# ST_Link.net
KiCad netlist of a schematic drawn in Altium Designer
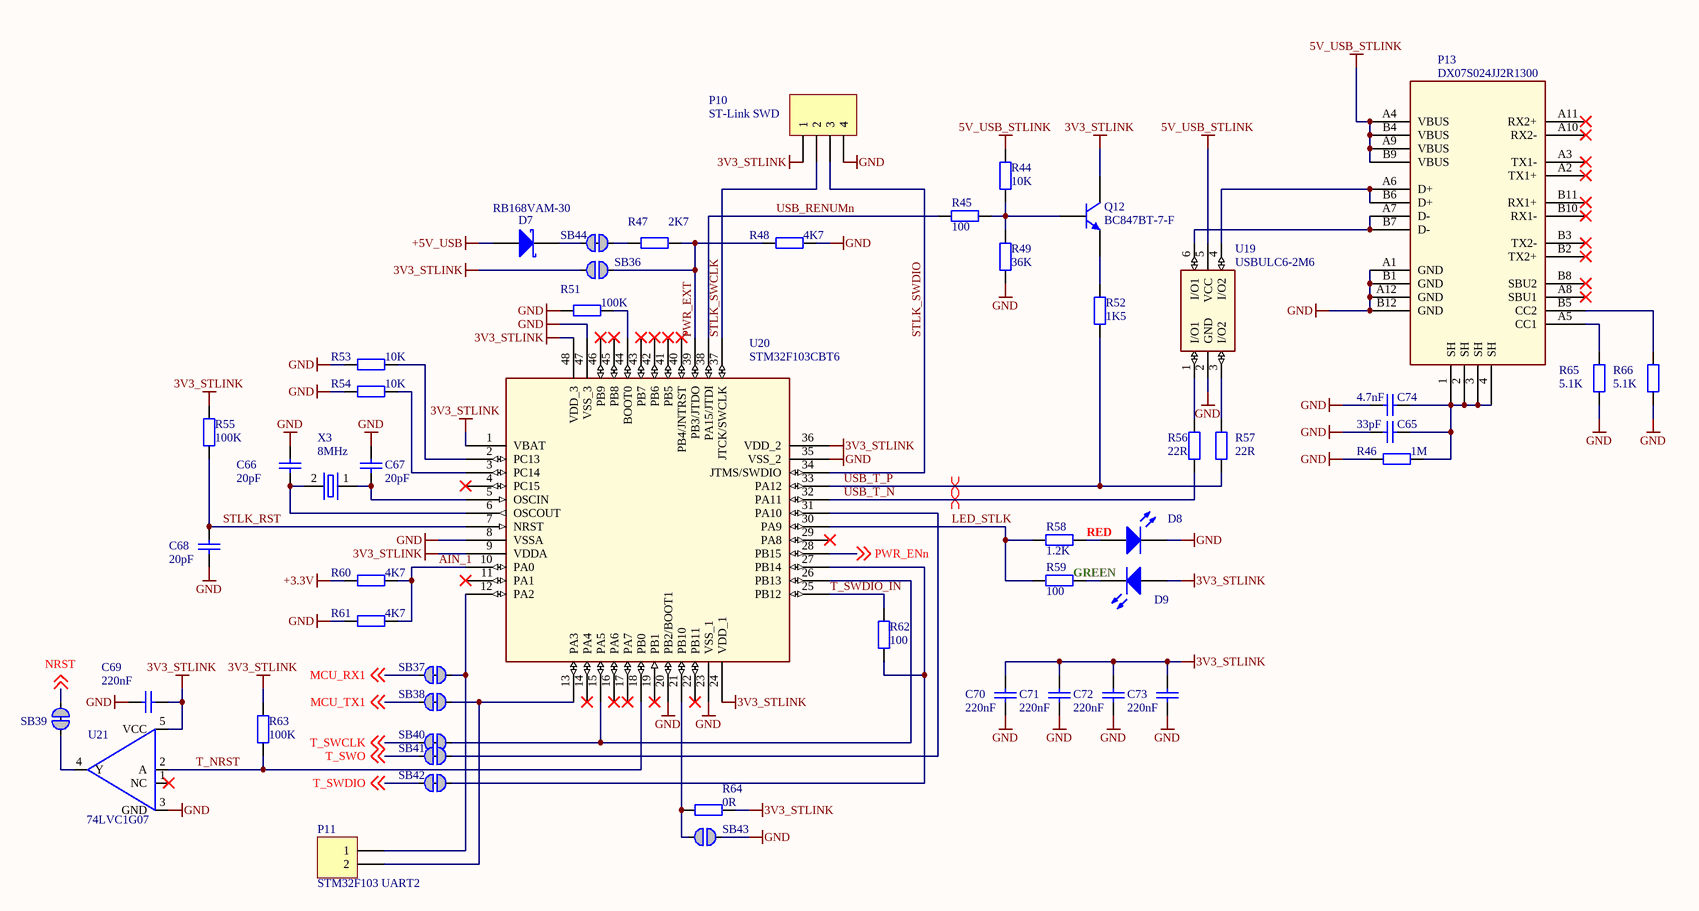
[diagram p0: ST Link.SchDoc]

(export (version "E")
  (design (tool "Eeschema 10.0.6"))
  (components
    (comp (ref "C65")
      (value "33pF")
      (footprint "C0402")
      (description "Capacitor (Semiconductor SIM Model)")
      (fields
        (field (name "MANUFACTURER") "YAGEO")
        (field (name "MANUFACTURER PART NO.") "CC0402JRNPO9BN100")
      )
      (libsource (lib "Miscellaneous Devices") (part "Cap Semi"))
    )
    (comp (ref "C66")
      (value "20pF")
      (footprint "C0402")
      (description "Capacitor (Semiconductor SIM Model)")
      (fields
        (field (name "MANUFACTURER") "YAGEO")
        (field (name "MANUFACTURER PART NO.") "CC0402JRNPO9BN100")
      )
      (libsource (lib "Miscellaneous Devices") (part "Cap Semi"))
    )
    (comp (ref "C67")
      (value "20pF")
      (footprint "C0402")
      (description "Capacitor (Semiconductor SIM Model)")
      (fields
        (field (name "MANUFACTURER") "YAGEO")
        (field (name "MANUFACTURER PART NO.") "CC0402JRNPO9BN100")
      )
      (libsource (lib "Miscellaneous Devices") (part "Cap Semi"))
    )
    (comp (ref "C68")
      (value "20pF")
      (footprint "C0402")
      (description "Capacitor (Semiconductor SIM Model)")
      (fields
        (field (name "MANUFACTURER") "YAGEO")
        (field (name "MANUFACTURER PART NO.") "CC0402JRNPO9BN100")
      )
      (libsource (lib "Miscellaneous Devices") (part "Cap Semi"))
    )
    (comp (ref "C69")
      (value "220nF")
      (footprint "C0402")
      (description "Capacitor (Semiconductor SIM Model)")
      (fields
        (field (name "MANUFACTURER") "YAGEO")
        (field (name "MANUFACTURER PART NO.") "CC0402JRNPO9BN100")
      )
      (libsource (lib "Miscellaneous Devices") (part "Cap Semi"))
    )
    (comp (ref "C70")
      (value "220nF")
      (footprint "C0402")
      (description "Capacitor (Semiconductor SIM Model)")
      (fields
        (field (name "MANUFACTURER") "YAGEO")
        (field (name "MANUFACTURER PART NO.") "CC0402JRNPO9BN100")
      )
      (libsource (lib "Miscellaneous Devices") (part "Cap Semi"))
    )
    (comp (ref "C71")
      (value "220nF")
      (footprint "C0402")
      (description "Capacitor (Semiconductor SIM Model)")
      (fields
        (field (name "MANUFACTURER") "YAGEO")
        (field (name "MANUFACTURER PART NO.") "CC0402JRNPO9BN100")
      )
      (libsource (lib "Miscellaneous Devices") (part "Cap Semi"))
    )
    (comp (ref "C72")
      (value "220nF")
      (footprint "C0402")
      (description "Capacitor (Semiconductor SIM Model)")
      (fields
        (field (name "MANUFACTURER") "YAGEO")
        (field (name "MANUFACTURER PART NO.") "CC0402JRNPO9BN100")
      )
      (libsource (lib "Miscellaneous Devices") (part "Cap Semi"))
    )
    (comp (ref "C73")
      (value "220nF")
      (footprint "C0402")
      (description "Capacitor (Semiconductor SIM Model)")
      (fields
        (field (name "MANUFACTURER") "YAGEO")
        (field (name "MANUFACTURER PART NO.") "CC0402JRNPO9BN100")
      )
      (libsource (lib "Miscellaneous Devices") (part "Cap Semi"))
    )
    (comp (ref "C74")
      (value "4.7nF")
      (footprint "C0402")
      (description "Capacitor (Semiconductor SIM Model)")
      (fields
        (field (name "MANUFACTURER") "YAGEO")
        (field (name "MANUFACTURER PART NO.") "CC0402JRNPO9BN100")
      )
      (libsource (lib "Miscellaneous Devices") (part "Cap Semi"))
    )
    (comp (ref "D7")
      (value "RB168VAM-30")
      (footprint "SOD323")
      (description "Schottky Diode")
      (fields (field (name "MANUFACTURER") "ROHM"))
      (libsource (lib "Miscellaneous Devices") (part "D Schottky"))
    )
    (comp (ref "D8")
      (value "LED")
      (footprint "PICOLED")
      (description "Typical SMD LED")
      (fields (field (name "MANUFACTURER") "ROHM") (field (name "MANUFACTURER PART NO.") "SML-P12UTT86"))
      (libsource (lib "Miscellaneous Devices") (part "LED2"))
    )
    (comp (ref "D9")
      (value "LED")
      (footprint "PICOLED")
      (description "Typical SMD LED")
      (fields (field (name "MANUFACTURER") "ROHM") (field (name "MANUFACTURER PART NO.") "SML-P13PTT86R"))
      (libsource (lib "Miscellaneous Devices") (part "LED2"))
    )
    (comp (ref "P10")
      (value "ST-Link SWD")
      (footprint "HDR1X4")
      (description "Header, 4-Pin")
      (libsource (lib "Miscellaneous Connectors") (part "Header 4"))
    )
    (comp (ref "P11")
      (value "STM32F103 UART2")
      (footprint "HDR1X2")
      (description "Header, 2-Pin")
      (libsource (lib "Miscellaneous Connectors") (part "Header 2"))
    )
    (comp (ref "P13")
      (value "DX07S024JJ2R1300")
      (footprint "DX07_USB_C")
      (description "24P USB C DUAL SMT ON BOARD")
      (fields (field (name "MANUFACTURER") "JAE"))
      (libsource (lib "DX07S024JJ2R1300") (part "DX07S024JJ2R1300"))
    )
    (comp (ref "Q12")
      (value "BC847BT-7-F")
      (footprint "SOT-523_custom")
      (description "NPN Bipolar Transistor")
      (fields
        (field (name "MANUFACTURER") "Diodes Inc.")
        (field (name "MANUFACTURER PART NO.") "BC847AT-7-F")
      )
      (libsource (lib "RUT2CLOUDPrjPcb") (part "NPN"))
    )
    (comp (ref "R44")
      (value "10K")
      (footprint "R0402")
      (fields
        (field (name "MANUFACTURER") "ASJ")
        (field (name "MANUFACTURER PART NO.") "CR10-103-JK")
        (field (name "Comment") "Res2")
      )
      (libsource (lib "Miscellaneous Devices") (part "Res2"))
    )
    (comp (ref "R45")
      (value "100")
      (footprint "R0402")
      (fields
        (field (name "MANUFACTURER") "ASJ")
        (field (name "MANUFACTURER PART NO.") "CR10-103-JK")
        (field (name "Comment") "Res2")
      )
      (libsource (lib "") (part "Res2_2"))
    )
    (comp (ref "R46")
      (value "1M")
      (footprint "R0402")
      (fields
        (field (name "MANUFACTURER") "YAGEO")
        (field (name "MANUFACTURER PART NO.") "RC0402FR-070RL")
        (field (name "Comment") "Res2")
      )
      (libsource (lib "") (part "Res2_1"))
    )
    (comp (ref "R47")
      (value "2K7")
      (footprint "R0402")
      (fields
        (field (name "MANUFACTURER") "ASJ")
        (field (name "MANUFACTURER PART NO.") "CR10-103-JK")
        (field (name "Comment") "Res2")
      )
      (libsource (lib "") (part "Res2_2"))
    )
    (comp (ref "R48")
      (value "4K7")
      (footprint "R0402")
      (fields
        (field (name "MANUFACTURER") "ASJ")
        (field (name "MANUFACTURER PART NO.") "CR10-103-JK")
        (field (name "Comment") "Res2")
      )
      (libsource (lib "") (part "Res2_2"))
    )
    (comp (ref "R49")
      (value "36K")
      (footprint "R0402")
      (fields
        (field (name "MANUFACTURER") "ASJ")
        (field (name "MANUFACTURER PART NO.") "CR10-103-JK")
        (field (name "Comment") "Res2")
      )
      (libsource (lib "Miscellaneous Devices") (part "Res2"))
    )
    (comp (ref "R51")
      (value "100K")
      (footprint "R0402")
      (fields
        (field (name "MANUFACTURER") "ASJ")
        (field (name "MANUFACTURER PART NO.") "CR10-103-JK")
        (field (name "Comment") "Res2")
      )
      (libsource (lib "") (part "Res2_2"))
    )
    (comp (ref "R52")
      (value "1K5")
      (footprint "R0402")
      (fields
        (field (name "MANUFACTURER") "ASJ")
        (field (name "MANUFACTURER PART NO.") "CR10-103-JK")
        (field (name "Comment") "Res2")
      )
      (libsource (lib "Miscellaneous Devices") (part "Res2"))
    )
    (comp (ref "R53")
      (value "10K")
      (footprint "R0402")
      (fields
        (field (name "MANUFACTURER") "ASJ")
        (field (name "MANUFACTURER PART NO.") "CR10-103-JK")
        (field (name "Comment") "Res2")
      )
      (libsource (lib "") (part "Res2_2"))
    )
    (comp (ref "R54")
      (value "10K")
      (footprint "R0402")
      (fields
        (field (name "MANUFACTURER") "ASJ")
        (field (name "MANUFACTURER PART NO.") "CR10-103-JK")
        (field (name "Comment") "Res2")
      )
      (libsource (lib "") (part "Res2_2"))
    )
    (comp (ref "R55")
      (value "100K")
      (footprint "R0402")
      (fields
        (field (name "MANUFACTURER") "ASJ")
        (field (name "MANUFACTURER PART NO.") "CR10-103-JK")
        (field (name "Comment") "Res2")
      )
      (libsource (lib "") (part "Res2_3"))
    )
    (comp (ref "R56")
      (value "22R")
      (footprint "R0402")
      (fields
        (field (name "MANUFACTURER") "ASJ")
        (field (name "MANUFACTURER PART NO.") "CR10-103-JK")
        (field (name "Comment") "Res2")
      )
      (libsource (lib "Miscellaneous Devices") (part "Res2"))
    )
    (comp (ref "R57")
      (value "22R")
      (footprint "R0402")
      (fields
        (field (name "MANUFACTURER") "ASJ")
        (field (name "MANUFACTURER PART NO.") "CR10-103-JK")
        (field (name "Comment") "Res2")
      )
      (libsource (lib "Miscellaneous Devices") (part "Res2"))
    )
    (comp (ref "R58")
      (value "1.2K")
      (footprint "R0402")
      (fields
        (field (name "MANUFACTURER") "ASJ")
        (field (name "MANUFACTURER PART NO.") "CR10-103-JK")
        (field (name "Comment") "Res2")
      )
      (libsource (lib "") (part "Res2_1"))
    )
    (comp (ref "R59")
      (value "100")
      (footprint "R0402")
      (fields
        (field (name "MANUFACTURER") "ASJ")
        (field (name "MANUFACTURER PART NO.") "CR10-103-JK")
        (field (name "Comment") "Res2")
      )
      (libsource (lib "") (part "Res2_1"))
    )
    (comp (ref "R60")
      (value "4K7")
      (footprint "R0402")
      (fields
        (field (name "MANUFACTURER") "ASJ")
        (field (name "MANUFACTURER PART NO.") "CR10-103-JK")
        (field (name "Comment") "Res2")
      )
      (libsource (lib "") (part "Res2_2"))
    )
    (comp (ref "R61")
      (value "4K7")
      (footprint "R0402")
      (fields
        (field (name "MANUFACTURER") "ASJ")
        (field (name "MANUFACTURER PART NO.") "CR10-103-JK")
        (field (name "Comment") "Res2")
      )
      (libsource (lib "") (part "Res2_2"))
    )
    (comp (ref "R62")
      (value "100")
      (footprint "R0402")
      (fields
        (field (name "MANUFACTURER") "ASJ")
        (field (name "MANUFACTURER PART NO.") "CR10-103-JK")
        (field (name "Comment") "Res2")
      )
      (libsource (lib "") (part "Res2_3"))
    )
    (comp (ref "R63")
      (value "100K")
      (footprint "R0402")
      (fields
        (field (name "MANUFACTURER") "ASJ")
        (field (name "MANUFACTURER PART NO.") "CR10-103-JK")
        (field (name "Comment") "Res2")
      )
      (libsource (lib "") (part "Res2_3"))
    )
    (comp (ref "R64")
      (value "0R")
      (footprint "R0402")
      (fields
        (field (name "MANUFACTURER") "ASJ")
        (field (name "MANUFACTURER PART NO.") "CR10-103-JK")
        (field (name "Comment") "Res2")
      )
      (libsource (lib "") (part "Res2_2"))
    )
    (comp (ref "R65")
      (value "5.1K")
      (footprint "R0402")
      (fields
        (field (name "MANUFACTURER") "ASJ")
        (field (name "MANUFACTURER PART NO.") "CR10-103-JK")
        (field (name "Comment") "Res2")
      )
      (libsource (lib "Miscellaneous Devices") (part "Res2"))
    )
    (comp (ref "R66")
      (value "5.1K")
      (footprint "R0402")
      (fields
        (field (name "MANUFACTURER") "ASJ")
        (field (name "MANUFACTURER PART NO.") "CR10-103-JK")
        (field (name "Comment") "Res2")
      )
      (libsource (lib "Miscellaneous Devices") (part "Res2"))
    )
    (comp (ref "SB36")
      (value "Solderbridge")
      (footprint "Solderbridge")
      (libsource (lib "altium-import") (part "root_2_SOLDERBRIDGE_"))
    )
    (comp (ref "SB37")
      (value "Solderbridge")
      (footprint "Solderbridge_Shorted")
      (libsource (lib "altium-import") (part "root_2_SOLDERBRIDGE_SHORTED_"))
    )
    (comp (ref "SB38")
      (value "Solderbridge")
      (footprint "Solderbridge_Shorted")
      (libsource (lib "altium-import") (part "root_2_SOLDERBRIDGE_SHORTED_"))
    )
    (comp (ref "SB39")
      (value "Solderbridge")
      (footprint "Solderbridge_Shorted")
      (libsource (lib "altium-import") (part "root_3_SOLDERBRIDGE_SHORTED_"))
    )
    (comp (ref "SB40")
      (value "Solderbridge")
      (footprint "Solderbridge_Shorted")
      (libsource (lib "altium-import") (part "root_2_SOLDERBRIDGE_SHORTED_"))
    )
    (comp (ref "SB41")
      (value "Solderbridge")
      (footprint "Solderbridge_Shorted")
      (libsource (lib "altium-import") (part "root_2_SOLDERBRIDGE_SHORTED_"))
    )
    (comp (ref "SB42")
      (value "Solderbridge")
      (footprint "Solderbridge_Shorted")
      (libsource (lib "altium-import") (part "root_2_SOLDERBRIDGE_SHORTED_"))
    )
    (comp (ref "SB43")
      (value "Solderbridge")
      (footprint "Solderbridge")
      (libsource (lib "altium-import") (part "root_2_SOLDERBRIDGE_"))
    )
    (comp (ref "SB44")
      (value "Solderbridge")
      (footprint "Solderbridge_Shorted")
      (libsource (lib "altium-import") (part "root_2_SOLDERBRIDGE_SHORTED_"))
    )
    (comp (ref "U19")
      (value "USBULC6-2M6")
      (footprint "Micro_QFN_6L")
      (description "Ultra large bandwidth ESD protection")
      (fields (field (name "MANUFACTURER") "STMicroelectronics"))
      (libsource (lib "USBULC6-2M6") (part "USBULC6-2M6"))
    )
    (comp (ref "U20")
      (value "STM32F103CBT6")
      (footprint "QFP48 7X7")
      (description "Medium-density performance line ARM-based 32-bit MCU with 64KB Flash")
      (fields (field (name "MANUFACTURER") "STMicroelectronics"))
      (libsource (lib "STM32F401_Nucleo") (part "STM32F103CBT6"))
    )
    (comp (ref "U21")
      (value "74LVC1G07")
      (footprint "X2-DFN1410-6")
      (description "SINGLE BUFFER/DRIVER WITH OPEN DRAIN OUTPUT")
      (fields
        (field (name "MANUFACTURER") "STMicroelectronics")
        (field (name "MANUFACTURER PART NO.") "74LVC1G07FZ4-7")
      )
      (libsource (lib "74LVC1G07") (part "74LVC1G07"))
    )
    (comp (ref "X3")
      (value "8MHz")
      (footprint "crystal_5032")
      (fields
        (field (name "MANUFACTURER") "Kyocera")
        (field (name "MANUFACTURER PART NO.") "CX5032GB08000H0HEQZ1")
      )
      (libsource (lib "RUT_L865_Project_1") (part "XTL-000011-01"))
    )
  )
  (nets
    (net (code "1") (name "+3.3V") (class "Default")
      (node (ref "R60") (pin "2") (pinfunction "2_2") (pintype "passive"))
    )
    (net (code "2") (name "+5V_USB") (class "Default")
      (node (ref "D7") (pin "1") (pinfunction "A_1") (pintype "passive"))
    )
    (net (code "3") (name "/AIN_1") (class "Default")
      (node (ref "R60") (pin "1") (pinfunction "1_1") (pintype "passive"))
      (node (ref "R61") (pin "1") (pinfunction "1_1") (pintype "passive"))
      (node (ref "U20") (pin "10") (pinfunction "PA0_10") (pintype "bidirectional"))
    )
    (net (code "4") (name "/LED_STLK") (class "Default")
      (node (ref "R58") (pin "1") (pinfunction "1_1") (pintype "passive"))
      (node (ref "R59") (pin "1") (pinfunction "1_1") (pintype "passive"))
      (node (ref "U20") (pin "30") (pinfunction "PA9_30") (pintype "bidirectional"))
    )
    (net (code "5") (name "/PWR_EXT") (class "Default")
      (node (ref "R47") (pin "1") (pinfunction "1_1") (pintype "passive"))
      (node (ref "R48") (pin "2") (pinfunction "2_2") (pintype "passive"))
      (node (ref "SB36") (pin "2") (pinfunction "1_2") (pintype "passive"))
      (node (ref "U20") (pin "39") (pinfunction "PB3/JTDO_39") (pintype "bidirectional"))
    )
    (net (code "6") (name "/STLK_RST") (class "Default")
      (node (ref "C68") (pin "2") (pinfunction "2_2") (pintype "passive"))
      (node (ref "R55") (pin "2") (pinfunction "2_2") (pintype "passive"))
      (node (ref "U20") (pin "7") (pinfunction "NRST_7") (pintype "input"))
    )
    (net (code "7") (name "/STLK_SWCLK") (class "Default")
      (node (ref "P10") (pin "2") (pinfunction "2_2") (pintype "passive"))
      (node (ref "U20") (pin "37") (pinfunction "JTCK/SWCLK_37") (pintype "bidirectional"))
    )
    (net (code "8") (name "/STLK_SWDIO") (class "Default")
      (node (ref "P10") (pin "3") (pinfunction "3_3") (pintype "passive"))
      (node (ref "U20") (pin "34") (pinfunction "JTMS/SWDIO_34") (pintype "bidirectional"))
    )
    (net (code "9") (name "/T_NRST") (class "Default")
      (node (ref "R63") (pin "2") (pinfunction "2_2") (pintype "passive"))
      (node (ref "U20") (pin "18") (pinfunction "PB0_18") (pintype "bidirectional"))
      (node (ref "U21") (pin "2") (pinfunction "A_2") (pintype "passive"))
    )
    (net (code "10") (name "/T_SWDIO_IN") (class "Default")
      (node (ref "R62") (pin "1") (pinfunction "1_1") (pintype "passive"))
      (node (ref "U20") (pin "25") (pinfunction "PB12_25") (pintype "bidirectional"))
    )
    (net (code "11") (name "/USB_RENUMn") (class "Default")
      (node (ref "R45") (pin "2") (pinfunction "2_2") (pintype "passive"))
      (node (ref "U20") (pin "38") (pinfunction "PA15/JTDI_38") (pintype "bidirectional"))
    )
    (net (code "12") (name "/USB_T_N") (class "Default")
      (node (ref "R56") (pin "1") (pinfunction "1_1") (pintype "passive"))
      (node (ref "U20") (pin "32") (pinfunction "PA11_32") (pintype "bidirectional"))
    )
    (net (code "13") (name "/USB_T_P") (class "Default")
      (node (ref "R52") (pin "1") (pinfunction "1_1") (pintype "passive"))
      (node (ref "R57") (pin "1") (pinfunction "1_1") (pintype "passive"))
      (node (ref "U20") (pin "33") (pinfunction "PA12_33") (pintype "bidirectional"))
    )
    (net (code "14") (name "3V3_STLINK") (class "Default")
      (node (ref "C69") (pin "2") (pinfunction "2_2") (pintype "passive"))
      (node (ref "C70") (pin "2") (pinfunction "2_2") (pintype "passive"))
      (node (ref "C71") (pin "2") (pinfunction "2_2") (pintype "passive"))
      (node (ref "C72") (pin "2") (pinfunction "2_2") (pintype "passive"))
      (node (ref "C73") (pin "2") (pinfunction "2_2") (pintype "passive"))
      (node (ref "D9") (pin "1") (pinfunction "A_1") (pintype "passive"))
      (node (ref "P10") (pin "1") (pinfunction "1_1") (pintype "passive"))
      (node (ref "Q12") (pin "2") (pinfunction "C_2") (pintype "passive"))
      (node (ref "R55") (pin "1") (pinfunction "1_1") (pintype "passive"))
      (node (ref "R63") (pin "1") (pinfunction "1_1") (pintype "passive"))
      (node (ref "R64") (pin "1") (pinfunction "1_1") (pintype "passive"))
      (node (ref "SB36") (pin "1") (pinfunction "0_1") (pintype "passive"))
      (node (ref "U20") (pin "1") (pinfunction "VBAT_1") (pintype "power_in"))
      (node (ref "U20") (pin "24") (pinfunction "VDD_1_24") (pintype "power_in"))
      (node (ref "U20") (pin "36") (pinfunction "VDD_2_36") (pintype "power_in"))
      (node (ref "U20") (pin "48") (pinfunction "VDD_3_48") (pintype "power_in"))
      (node (ref "U20") (pin "9") (pinfunction "VDDA_9") (pintype "power_in"))
      (node (ref "U21") (pin "5") (pinfunction "VCC_5") (pintype "passive"))
    )
    (net (code "15") (name "5V_USB_STLINK") (class "Default")
      (node (ref "P13") (pin "A4") (pinfunction "VBUS_A4") (pintype "passive"))
      (node (ref "P13") (pin "A9") (pinfunction "VBUS_A9") (pintype "passive"))
      (node (ref "P13") (pin "B4") (pinfunction "VBUS_B4") (pintype "passive"))
      (node (ref "P13") (pin "B9") (pinfunction "VBUS_B9") (pintype "passive"))
      (node (ref "R44") (pin "2") (pinfunction "2_2") (pintype "passive"))
      (node (ref "U19") (pin "5") (pinfunction "VCC_5") (pintype "power_in"))
    )
    (net (code "16") (name "GND") (class "Default")
      (node (ref "C65") (pin "1") (pinfunction "1_1") (pintype "passive"))
      (node (ref "C66") (pin "2") (pinfunction "2_2") (pintype "passive"))
      (node (ref "C67") (pin "2") (pinfunction "2_2") (pintype "passive"))
      (node (ref "C68") (pin "1") (pinfunction "1_1") (pintype "passive"))
      (node (ref "C69") (pin "1") (pinfunction "1_1") (pintype "passive"))
      (node (ref "C70") (pin "1") (pinfunction "1_1") (pintype "passive"))
      (node (ref "C71") (pin "1") (pinfunction "1_1") (pintype "passive"))
      (node (ref "C72") (pin "1") (pinfunction "1_1") (pintype "passive"))
      (node (ref "C73") (pin "1") (pinfunction "1_1") (pintype "passive"))
      (node (ref "C74") (pin "1") (pinfunction "1_1") (pintype "passive"))
      (node (ref "D8") (pin "2") (pinfunction "K_2") (pintype "passive"))
      (node (ref "P10") (pin "4") (pinfunction "4_4") (pintype "passive"))
      (node (ref "P13") (pin "A1") (pinfunction "GND_A1") (pintype "passive"))
      (node (ref "P13") (pin "A12") (pinfunction "GND_A12") (pintype "passive"))
      (node (ref "P13") (pin "B1") (pinfunction "GND_B1") (pintype "passive"))
      (node (ref "P13") (pin "B12") (pinfunction "GND_B12") (pintype "passive"))
      (node (ref "R46") (pin "1") (pinfunction "1_1") (pintype "passive"))
      (node (ref "R48") (pin "1") (pinfunction "1_1") (pintype "passive"))
      (node (ref "R49") (pin "1") (pinfunction "1_1") (pintype "passive"))
      (node (ref "R51") (pin "2") (pinfunction "2_2") (pintype "passive"))
      (node (ref "R53") (pin "2") (pinfunction "2_2") (pintype "passive"))
      (node (ref "R54") (pin "2") (pinfunction "2_2") (pintype "passive"))
      (node (ref "R61") (pin "2") (pinfunction "2_2") (pintype "passive"))
      (node (ref "R65") (pin "1") (pinfunction "1_1") (pintype "passive"))
      (node (ref "R66") (pin "1") (pinfunction "1_1") (pintype "passive"))
      (node (ref "SB43") (pin "2") (pinfunction "1_2") (pintype "passive"))
      (node (ref "U19") (pin "2") (pinfunction "GND_2") (pintype "power_in"))
      (node (ref "U20") (pin "20") (pinfunction "PB2/BOOT1_20") (pintype "bidirectional"))
      (node (ref "U20") (pin "23") (pinfunction "VSS_1_23") (pintype "power_in"))
      (node (ref "U20") (pin "35") (pinfunction "VSS_2_35") (pintype "power_in"))
      (node (ref "U20") (pin "47") (pinfunction "VSS_3_47") (pintype "power_in"))
      (node (ref "U20") (pin "8") (pinfunction "VSSA_8") (pintype "power_in"))
      (node (ref "U21") (pin "3") (pinfunction "GND_3") (pintype "passive"))
    )
    (net (code "17") (name "MCU_RX1") (class "Default")
      (node (ref "SB37") (pin "1") (pinfunction "0_1") (pintype "passive"))
    )
    (net (code "18") (name "MCU_TX1") (class "Default")
      (node (ref "SB38") (pin "1") (pinfunction "0_1") (pintype "passive"))
    )
    (net (code "19") (name "NRST") (class "Default")
      (node (ref "SB39") (pin "2") (pinfunction "1_2") (pintype "passive"))
    )
    (net (code "20") (name "Net-(C65-Pad2)") (class "Default")
      (node (ref "C65") (pin "2") (pinfunction "2_2") (pintype "passive"))
      (node (ref "C74") (pin "2") (pinfunction "2_2") (pintype "passive"))
      (node (ref "P13") (pin "1") (pinfunction "SH_1") (pintype "passive"))
      (node (ref "P13") (pin "2") (pinfunction "SH_2") (pintype "passive"))
      (node (ref "P13") (pin "3") (pinfunction "SH_3") (pintype "passive"))
      (node (ref "P13") (pin "4") (pinfunction "SH_4") (pintype "passive"))
      (node (ref "R46") (pin "2") (pinfunction "2_2") (pintype "passive"))
    )
    (net (code "21") (name "Net-(D7-K)") (class "Default")
      (node (ref "D7") (pin "2") (pinfunction "K_2") (pintype "passive"))
      (node (ref "SB44") (pin "1") (pinfunction "0_1") (pintype "passive"))
    )
    (net (code "22") (name "Net-(D8-A)") (class "Default")
      (node (ref "D8") (pin "1") (pinfunction "A_1") (pintype "passive"))
      (node (ref "R58") (pin "2") (pinfunction "2_2") (pintype "passive"))
    )
    (net (code "23") (name "Net-(D9-K)") (class "Default")
      (node (ref "D9") (pin "2") (pinfunction "K_2") (pintype "passive"))
      (node (ref "R59") (pin "2") (pinfunction "2_2") (pintype "passive"))
    )
    (net (code "24") (name "Net-(P13-CC1)") (class "Default")
      (node (ref "P13") (pin "A5") (pinfunction "CC1_A5") (pintype "passive"))
      (node (ref "R65") (pin "2") (pinfunction "2_2") (pintype "passive"))
    )
    (net (code "25") (name "Net-(P13-CC2)") (class "Default")
      (node (ref "P13") (pin "B5") (pinfunction "CC2_B5") (pintype "passive"))
      (node (ref "R66") (pin "2") (pinfunction "2_2") (pintype "passive"))
    )
    (net (code "26") (name "Net-(P13-D+-PadA6)") (class "Default")
      (node (ref "P13") (pin "A6") (pinfunction "D+_A6") (pintype "passive"))
      (node (ref "P13") (pin "B6") (pinfunction "D+_B6") (pintype "passive"))
      (node (ref "U19") (pin "4") (pinfunction "I/O2_4") (pintype "bidirectional"))
    )
    (net (code "27") (name "Net-(P13-D--PadA7)") (class "Default")
      (node (ref "P13") (pin "A7") (pinfunction "D-_A7") (pintype "passive"))
      (node (ref "P13") (pin "B7") (pinfunction "D-_B7") (pintype "passive"))
      (node (ref "U19") (pin "6") (pinfunction "I/O1_6") (pintype "bidirectional"))
    )
    (net (code "28") (name "Net-(Q12-B)") (class "Default")
      (node (ref "Q12") (pin "1") (pinfunction "B_1") (pintype "passive"))
      (node (ref "R44") (pin "1") (pinfunction "1_1") (pintype "passive"))
      (node (ref "R45") (pin "1") (pinfunction "1_1") (pintype "passive"))
      (node (ref "R49") (pin "2") (pinfunction "2_2") (pintype "passive"))
    )
    (net (code "29") (name "Net-(Q12-E)") (class "Default")
      (node (ref "Q12") (pin "3") (pinfunction "E_3") (pintype "passive"))
      (node (ref "R52") (pin "2") (pinfunction "2_2") (pintype "passive"))
    )
    (net (code "30") (name "Net-(R56-Pad2)") (class "Default")
      (node (ref "R56") (pin "2") (pinfunction "2_2") (pintype "passive"))
      (node (ref "U19") (pin "1") (pinfunction "I/O1_1") (pintype "bidirectional"))
    )
    (net (code "31") (name "Net-(R57-Pad2)") (class "Default")
      (node (ref "R57") (pin "2") (pinfunction "2_2") (pintype "passive"))
      (node (ref "U19") (pin "3") (pinfunction "I/O2_3") (pintype "bidirectional"))
    )
    (net (code "32") (name "Net-(SB37-1)") (class "Default")
      (node (ref "P11") (pin "1") (pinfunction "1_1") (pintype "passive"))
      (node (ref "SB37") (pin "2") (pinfunction "1_2") (pintype "passive"))
      (node (ref "U20") (pin "12") (pinfunction "PA2_12") (pintype "bidirectional"))
    )
    (net (code "33") (name "Net-(SB38-1)") (class "Default")
      (node (ref "P11") (pin "2") (pinfunction "2_2") (pintype "passive"))
      (node (ref "SB38") (pin "2") (pinfunction "1_2") (pintype "passive"))
      (node (ref "U20") (pin "13") (pinfunction "PA3_13") (pintype "bidirectional"))
    )
    (net (code "34") (name "Net-(SB39-0)") (class "Default")
      (node (ref "SB39") (pin "1") (pinfunction "0_1") (pintype "passive"))
      (node (ref "U21") (pin "4") (pinfunction "Y_4") (pintype "passive"))
    )
    (net (code "35") (name "Net-(SB40-1)") (class "Default")
      (node (ref "SB40") (pin "2") (pinfunction "1_2") (pintype "passive"))
      (node (ref "U20") (pin "15") (pinfunction "PA5_15") (pintype "bidirectional"))
      (node (ref "U20") (pin "26") (pinfunction "PB13_26") (pintype "bidirectional"))
    )
    (net (code "36") (name "Net-(SB41-1)") (class "Default")
      (node (ref "SB41") (pin "2") (pinfunction "1_2") (pintype "passive"))
      (node (ref "U20") (pin "31") (pinfunction "PA10_31") (pintype "bidirectional"))
    )
    (net (code "37") (name "Net-(SB42-1)") (class "Default")
      (node (ref "R62") (pin "2") (pinfunction "2_2") (pintype "passive"))
      (node (ref "SB42") (pin "2") (pinfunction "1_2") (pintype "passive"))
      (node (ref "U20") (pin "27") (pinfunction "PB14_27") (pintype "bidirectional"))
    )
    (net (code "38") (name "Net-(SB43-0)") (class "Default")
      (node (ref "R64") (pin "2") (pinfunction "2_2") (pintype "passive"))
      (node (ref "SB43") (pin "1") (pinfunction "0_1") (pintype "passive"))
      (node (ref "U20") (pin "21") (pinfunction "PB10_21") (pintype "bidirectional"))
    )
    (net (code "39") (name "Net-(SB44-1)") (class "Default")
      (node (ref "R47") (pin "2") (pinfunction "2_2") (pintype "passive"))
      (node (ref "SB44") (pin "2") (pinfunction "1_2") (pintype "passive"))
    )
    (net (code "40") (name "Net-(U20-BOOT0)") (class "Default")
      (node (ref "R51") (pin "1") (pinfunction "1_1") (pintype "passive"))
      (node (ref "U20") (pin "44") (pinfunction "BOOT0_44") (pintype "bidirectional"))
    )
    (net (code "41") (name "Net-(U20-OSCIN)") (class "Default")
      (node (ref "C67") (pin "1") (pinfunction "1_1") (pintype "passive"))
      (node (ref "U20") (pin "5") (pinfunction "OSCIN_5") (pintype "input"))
      (node (ref "X3") (pin "1") (pinfunction "1_1") (pintype "passive"))
    )
    (net (code "42") (name "Net-(U20-OSCOUT)") (class "Default")
      (node (ref "C66") (pin "1") (pinfunction "1_1") (pintype "passive"))
      (node (ref "U20") (pin "6") (pinfunction "OSCOUT_6") (pintype "output"))
      (node (ref "X3") (pin "2") (pinfunction "2_2") (pintype "passive"))
    )
    (net (code "43") (name "Net-(U20-PC13)") (class "Default")
      (node (ref "R53") (pin "1") (pinfunction "1_1") (pintype "passive"))
      (node (ref "U20") (pin "2") (pinfunction "PC13_2") (pintype "bidirectional"))
    )
    (net (code "44") (name "Net-(U20-PC14)") (class "Default")
      (node (ref "R54") (pin "1") (pinfunction "1_1") (pintype "passive"))
      (node (ref "U20") (pin "3") (pinfunction "PC14_3") (pintype "bidirectional"))
    )
    (net (code "45") (name "PWR_ENn") (class "Default")
      (node (ref "U20") (pin "28") (pinfunction "PB15_28") (pintype "bidirectional"))
    )
    (net (code "46") (name "T_SWCLK") (class "Default")
      (node (ref "SB40") (pin "1") (pinfunction "0_1") (pintype "passive"))
    )
    (net (code "47") (name "T_SWDIO") (class "Default")
      (node (ref "SB42") (pin "1") (pinfunction "0_1") (pintype "passive"))
    )
    (net (code "48") (name "T_SWO") (class "Default")
      (node (ref "SB41") (pin "1") (pinfunction "0_1") (pintype "passive"))
    )
    (net (code "49") (name "unconnected-(P13-RX1+-PadB11)") (class "Default")
      (node (ref "P13") (pin "B11") (pinfunction "RX1+_B11") (pintype "passive+no_connect"))
    )
    (net (code "50") (name "unconnected-(P13-RX1--PadB10)") (class "Default")
      (node (ref "P13") (pin "B10") (pinfunction "RX1-_B10") (pintype "passive+no_connect"))
    )
    (net (code "51") (name "unconnected-(P13-RX2+-PadA11)") (class "Default")
      (node (ref "P13") (pin "A11") (pinfunction "RX2+_A11") (pintype "passive+no_connect"))
    )
    (net (code "52") (name "unconnected-(P13-RX2--PadA10)") (class "Default")
      (node (ref "P13") (pin "A10") (pinfunction "RX2-_A10") (pintype "passive+no_connect"))
    )
    (net (code "53") (name "unconnected-(P13-SBU1-PadA8)") (class "Default")
      (node (ref "P13") (pin "A8") (pinfunction "SBU1_A8") (pintype "passive+no_connect"))
    )
    (net (code "54") (name "unconnected-(P13-SBU2-PadB8)") (class "Default")
      (node (ref "P13") (pin "B8") (pinfunction "SBU2_B8") (pintype "passive+no_connect"))
    )
    (net (code "55") (name "unconnected-(P13-TX1+-PadA2)") (class "Default")
      (node (ref "P13") (pin "A2") (pinfunction "TX1+_A2") (pintype "passive+no_connect"))
    )
    (net (code "56") (name "unconnected-(P13-TX1--PadA3)") (class "Default")
      (node (ref "P13") (pin "A3") (pinfunction "TX1-_A3") (pintype "passive+no_connect"))
    )
    (net (code "57") (name "unconnected-(P13-TX2+-PadB2)") (class "Default")
      (node (ref "P13") (pin "B2") (pinfunction "TX2+_B2") (pintype "passive+no_connect"))
    )
    (net (code "58") (name "unconnected-(P13-TX2--PadB3)") (class "Default")
      (node (ref "P13") (pin "B3") (pinfunction "TX2-_B3") (pintype "passive+no_connect"))
    )
    (net (code "59") (name "unconnected-(U20-PA1-Pad11)") (class "Default")
      (node (ref "U20") (pin "11") (pinfunction "PA1_11") (pintype "bidirectional+no_connect"))
    )
    (net (code "60") (name "unconnected-(U20-PA4-Pad14)") (class "Default")
      (node (ref "U20") (pin "14") (pinfunction "PA4_14") (pintype "bidirectional+no_connect"))
    )
    (net (code "61") (name "unconnected-(U20-PA6-Pad16)") (class "Default")
      (node (ref "U20") (pin "16") (pinfunction "PA6_16") (pintype "bidirectional+no_connect"))
    )
    (net (code "62") (name "unconnected-(U20-PA7-Pad17)") (class "Default")
      (node (ref "U20") (pin "17") (pinfunction "PA7_17") (pintype "bidirectional+no_connect"))
    )
    (net (code "63") (name "unconnected-(U20-PA8-Pad29)") (class "Default")
      (node (ref "U20") (pin "29") (pinfunction "PA8_29") (pintype "bidirectional+no_connect"))
    )
    (net (code "64") (name "unconnected-(U20-PB1-Pad19)") (class "Default")
      (node (ref "U20") (pin "19") (pinfunction "PB1_19") (pintype "input+no_connect"))
    )
    (net (code "65") (name "unconnected-(U20-PB4{slash}JNTRST-Pad40)") (class "Default")
      (node (ref "U20") (pin "40") (pinfunction "PB4/JNTRST_40") (pintype "bidirectional+no_connect"))
    )
    (net (code "66") (name "unconnected-(U20-PB5-Pad41)") (class "Default")
      (node (ref "U20") (pin "41") (pinfunction "PB5_41") (pintype "bidirectional+no_connect"))
    )
    (net (code "67") (name "unconnected-(U20-PB6-Pad42)") (class "Default")
      (node (ref "U20") (pin "42") (pinfunction "PB6_42") (pintype "bidirectional+no_connect"))
    )
    (net (code "68") (name "unconnected-(U20-PB7-Pad43)") (class "Default")
      (node (ref "U20") (pin "43") (pinfunction "PB7_43") (pintype "bidirectional+no_connect"))
    )
    (net (code "69") (name "unconnected-(U20-PB8-Pad45)") (class "Default")
      (node (ref "U20") (pin "45") (pinfunction "PB8_45") (pintype "bidirectional+no_connect"))
    )
    (net (code "70") (name "unconnected-(U20-PB9-Pad46)") (class "Default")
      (node (ref "U20") (pin "46") (pinfunction "PB9_46") (pintype "bidirectional+no_connect"))
    )
    (net (code "71") (name "unconnected-(U20-PB11-Pad22)") (class "Default")
      (node (ref "U20") (pin "22") (pinfunction "PB11_22") (pintype "bidirectional+no_connect"))
    )
    (net (code "72") (name "unconnected-(U20-PC15-Pad4)") (class "Default")
      (node (ref "U20") (pin "4") (pinfunction "PC15_4") (pintype "bidirectional+no_connect"))
    )
    (net (code "73") (name "unconnected-(U21-NC-Pad1)") (class "Default")
      (node (ref "U21") (pin "1") (pinfunction "NC_1") (pintype "passive+no_connect"))
    )
  )
)
